# LCL_1.net
KiCad netlist of a schematic drawn in Altium Designer
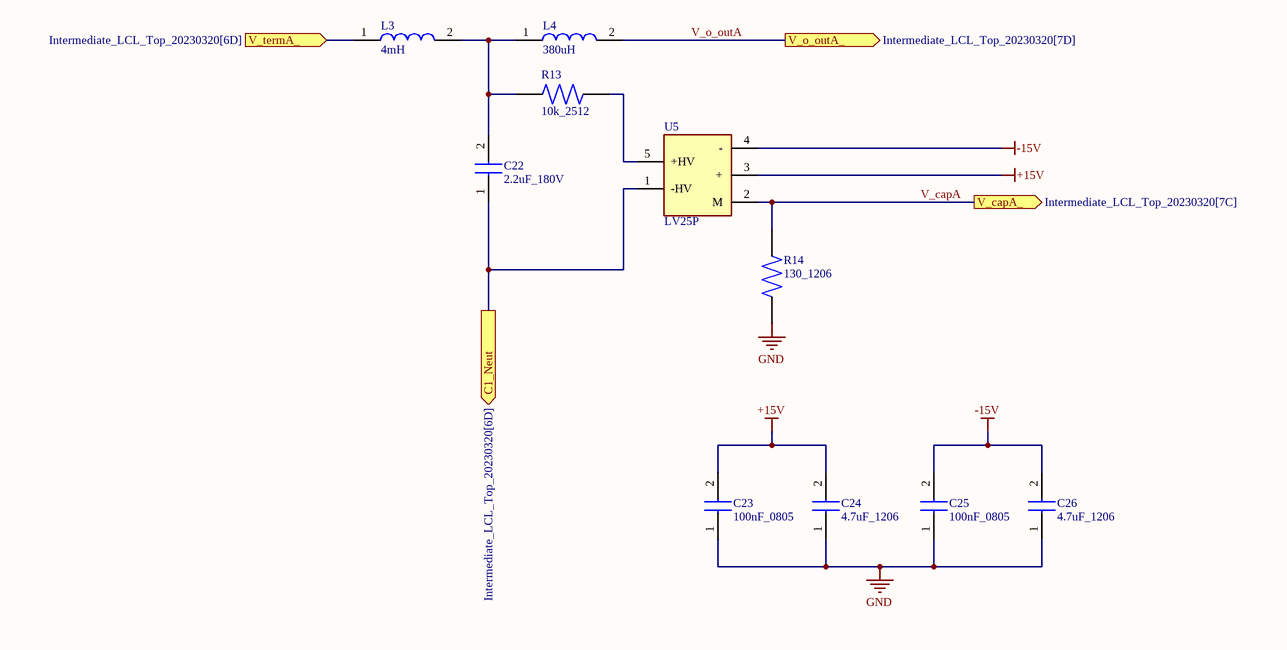
[diagram p0: LCL_1.SchDoc]

(export (version "E")
  (design (tool "Eeschema 10.0.6"))
  (components
    (comp (ref "C22")
      (value "2.2uF_180V")
      (footprint "Film Capacitor PHE450HF7220JR06L2")
      (description "KEMET PHE450 Metallised Polypropylene Film Capacitor, 180 V ac, 250 V dc, ±5%, 2.2μF, Through Hole")
      (fields (field (name "MANUFACTURER_PART_NUMBER") "PHE450HF7220JR06L2"))
      (libsource (lib "FYP_Components") (part "PHE450HF7220JR06L2"))
    )
    (comp (ref "C23")
      (value "100nF_0805")
      (footprint "0805 Capacitor")
      (description "SMD Multilayer Ceramic Capacitor, 0.1 µF, 50 V, 0805 [2012 Metric], ± 5%, X7R, C Series KEMET")
      (libsource (lib "FYP_Components") (part "C0805C104J5RACTU"))
    )
    (comp (ref "C24")
      (value "4.7uF_1206")
      (footprint "FYP_Components:1206 Capacitor")
      (description "SMD Multilayer Ceramic Capacitor, 4.7 µF, 50 V, 1206 [3216 Metric], ± 10%, X7R, C")
      (fields (field (name "MP") "C1206C120J5GACTU"))
      (libsource (lib "FYP_Components") (part "C3216X7R1H475K160AC"))
    )
    (comp (ref "C25")
      (value "100nF_0805")
      (footprint "0805 Capacitor")
      (description "SMD Multilayer Ceramic Capacitor, 0.1 µF, 50 V, 0805 [2012 Metric], ± 5%, X7R, C Series KEMET")
      (libsource (lib "FYP_Components") (part "C0805C104J5RACTU"))
    )
    (comp (ref "C26")
      (value "4.7uF_1206")
      (footprint "FYP_Components:1206 Capacitor")
      (description "SMD Multilayer Ceramic Capacitor, 4.7 µF, 50 V, 1206 [3216 Metric], ± 10%, X7R, C")
      (fields (field (name "MP") "C1206C120J5GACTU"))
      (libsource (lib "FYP_Components") (part "C3216X7R1H475K160AC"))
    )
    (comp (ref "L3")
      (value "4mH")
      (footprint "4mH Custom")
      (libsource (lib "FYP_Components") (part "4mH Custom Inductor"))
    )
    (comp (ref "L4")
      (value "380uH")
      (footprint "380uH Custom")
      (libsource (lib "FYP_Components") (part "380uH Custom Inductor"))
    )
    (comp (ref "R13")
      (value "10k_2512")
      (footprint "FYP_Components:2512 Resistor")
      (description "SMD Chip Resistor, 10 kohm, ± 1%, 2 W, 2512 [6432 Metric], Thick Film, High Power")
      (fields (field (name "MF") "Bourns") (field (name "MP") "CRE2512-FZ-R007E-3"))
      (libsource (lib "FYP_Components") (part "MCHP122WF1002T4E"))
    )
    (comp (ref "R14")
      (value "130_1206")
      (footprint "FYP_Components:1206 Resistor")
      (description "SMD Chip Resistor, 130 ohm, ± 1%, 250 mW, 1206 [3216 Metric], Thick Film, General Purpose")
      (fields (field (name "MF") "Bourns") (field (name "MP") "CRE2512-FZ-R007E-3"))
      (libsource (lib "FYP_Components") (part "CRCW1206130RFKEA"))
    )
    (comp (ref "U5")
      (value "LV25P")
      (footprint "FYP_Components:LV-25-P")
      (description "Undefined or Miscellaneous")
      (libsource (lib "FYP_Components") (part "LV25P"))
    )
  )
  (nets
    (net (code "1") (name "+15V") (class "Default")
      (node (ref "C23") (pin "2") (pinfunction "2_2") (pintype "passive"))
      (node (ref "C24") (pin "2") (pinfunction "2_2") (pintype "passive"))
      (node (ref "U5") (pin "3") (pinfunction "+_3") (pintype "passive"))
    )
    (net (code "2") (name "-15V") (class "Default")
      (node (ref "C25") (pin "2") (pinfunction "2_2") (pintype "passive"))
      (node (ref "C26") (pin "2") (pinfunction "2_2") (pintype "passive"))
      (node (ref "U5") (pin "4") (pinfunction "-_4") (pintype "passive"))
    )
    (net (code "3") (name "/C1_Neut") (class "Default")
      (node (ref "C22") (pin "1") (pinfunction "1_1") (pintype "passive"))
      (node (ref "U5") (pin "1") (pinfunction "-HV_1") (pintype "passive"))
    )
    (net (code "4") (name "/V_capA") (class "Default")
      (node (ref "R14") (pin "2") (pinfunction "2_2") (pintype "passive"))
      (node (ref "U5") (pin "2") (pinfunction "M_2") (pintype "passive"))
    )
    (net (code "5") (name "/V_o_outA") (class "Default")
      (node (ref "L4") (pin "2") (pinfunction "2_2") (pintype "passive"))
    )
    (net (code "6") (name "/V_termA_") (class "Default")
      (node (ref "L3") (pin "1") (pinfunction "1_1") (pintype "passive"))
    )
    (net (code "7") (name "GND") (class "Default")
      (node (ref "C23") (pin "1") (pinfunction "1_1") (pintype "passive"))
      (node (ref "C24") (pin "1") (pinfunction "1_1") (pintype "passive"))
      (node (ref "C25") (pin "1") (pinfunction "1_1") (pintype "passive"))
      (node (ref "C26") (pin "1") (pinfunction "1_1") (pintype "passive"))
      (node (ref "R14") (pin "1") (pinfunction "1_1") (pintype "passive"))
    )
    (net (code "8") (name "Net-(C22-Pad2)") (class "Default")
      (node (ref "C22") (pin "2") (pinfunction "2_2") (pintype "passive"))
      (node (ref "L3") (pin "2") (pinfunction "2_2") (pintype "passive"))
      (node (ref "L4") (pin "1") (pinfunction "1_1") (pintype "passive"))
      (node (ref "R13") (pin "1") (pinfunction "1_1") (pintype "passive"))
    )
    (net (code "9") (name "Net-(U5-+HV)") (class "Default")
      (node (ref "R13") (pin "2") (pinfunction "2_2") (pintype "passive"))
      (node (ref "U5") (pin "5") (pinfunction "+HV_5") (pintype "passive"))
    )
  )
)
